# Sheet1.net
KiCad netlist of a schematic drawn in Altium Designer
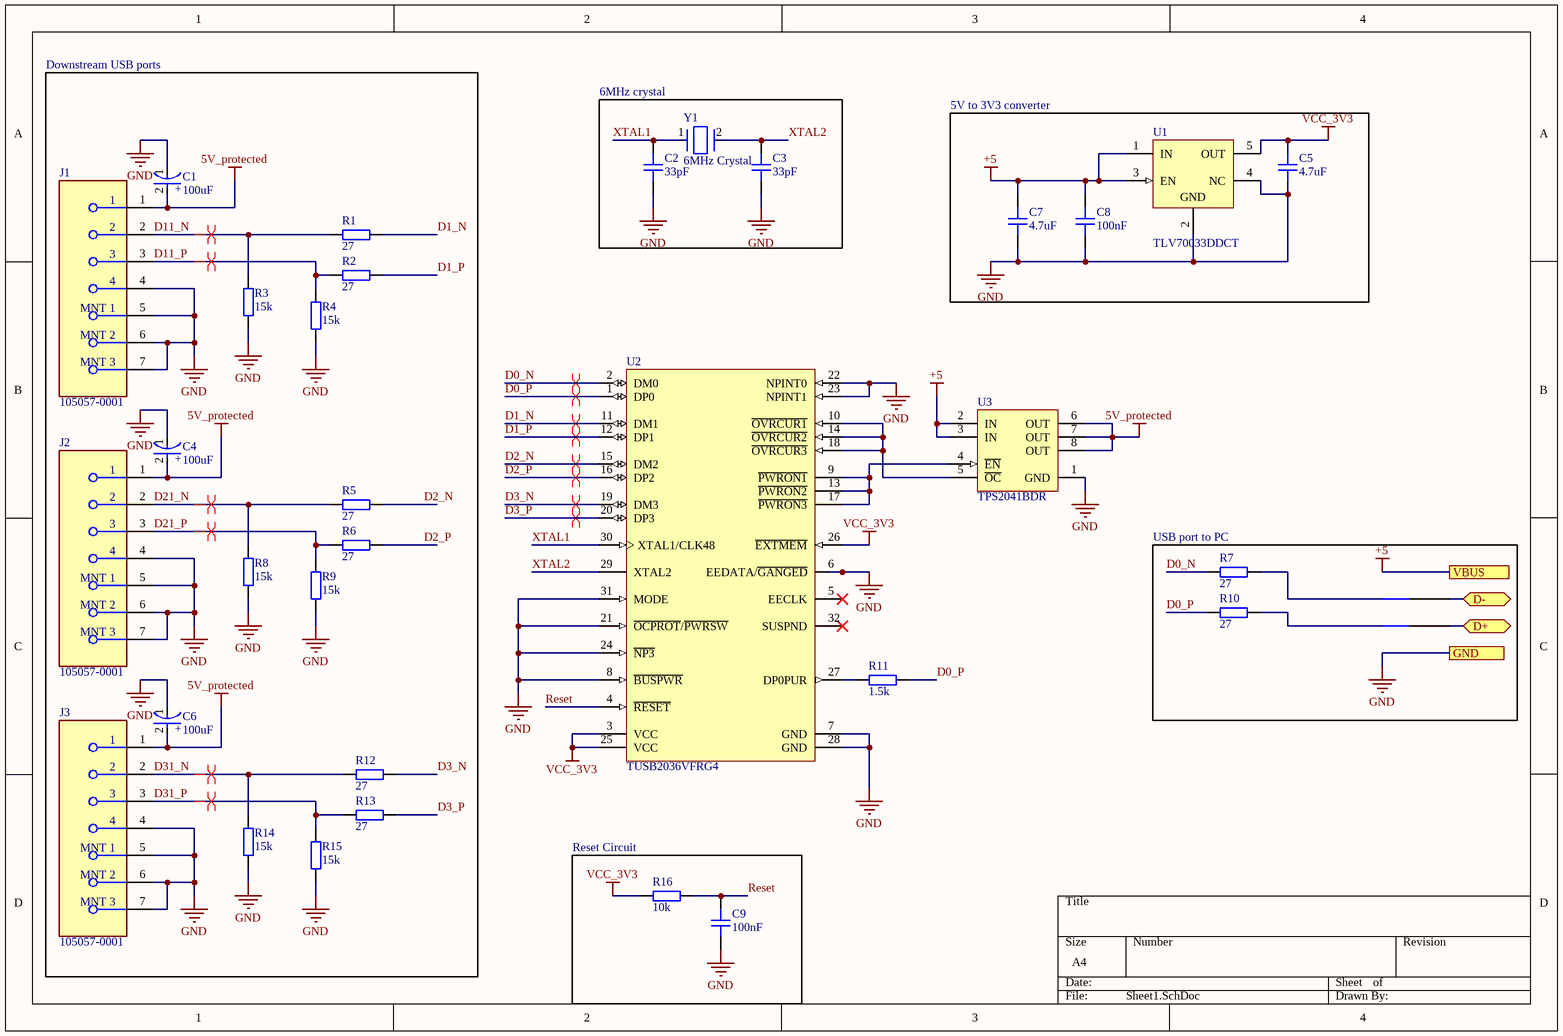
[diagram p0: Sheet1.SchDoc]

(export (version "E")
  (design (tool "Eeschema 10.0.6"))
  (components
    (comp (ref "C1")
      (value "100uF")
      (footprint "FP-TPSB-MFG")
      (description "CAP TANT 100UF 10% 6.3V 1411 TPSB107K006R0400")
      (fields (field (name "TOLERANCE") "10%") (field (name "VOLTAGE") "6.3V"))
      (libsource (lib "Altium Content Vault") (part "a00bbbee19879c290e62620ae7e47b1"))
    )
    (comp (ref "C2")
      (value "33pF")
      (footprint "CAP_0603")
      (description "Capacitor SMD 0603")
      (libsource (lib "Schematic-Lib-PhilsLab") (part "CAP_0603"))
    )
    (comp (ref "C3")
      (value "33pF")
      (footprint "CAP_0603")
      (description "Capacitor SMD 0603")
      (libsource (lib "Schematic-Lib-PhilsLab") (part "CAP_0603"))
    )
    (comp (ref "C4")
      (value "100uF")
      (footprint "FP-TPSB-MFG")
      (description "CAP TANT 100UF 10% 6.3V 1411 TPSB107K006R0400")
      (fields (field (name "TOLERANCE") "10%") (field (name "VOLTAGE") "6.3V"))
      (libsource (lib "Altium Content Vault") (part "a00bbbee19879c290e62620ae7e47b1"))
    )
    (comp (ref "C5")
      (value "4.7uF")
      (footprint "CAP_0603")
      (description "Capacitor SMD 0603")
      (libsource (lib "Schematic-Lib-PhilsLab") (part "CAP_0603"))
    )
    (comp (ref "C6")
      (value "100uF")
      (footprint "FP-TPSB-MFG")
      (description "CAP TANT 100UF 10% 6.3V 1411 TPSB107K006R0400")
      (fields (field (name "TOLERANCE") "10%") (field (name "VOLTAGE") "6.3V"))
      (libsource (lib "Altium Content Vault") (part "a00bbbee19879c290e62620ae7e47b1"))
    )
    (comp (ref "C7")
      (value "4.7uF")
      (footprint "CAP_0603")
      (description "Capacitor SMD 0603")
      (libsource (lib "Schematic-Lib-PhilsLab") (part "CAP_0603"))
    )
    (comp (ref "C8")
      (value "100nF")
      (footprint "CAP_0603")
      (description "Capacitor SMD 0603")
      (libsource (lib "Schematic-Lib-PhilsLab") (part "CAP_0603"))
    )
    (comp (ref "C9")
      (value "100nF")
      (footprint "CAP_0603")
      (description "Capacitor SMD 0603")
      (libsource (lib "Schematic-Lib-PhilsLab") (part "CAP_0603"))
    )
    (comp (ref "J1")
      (value "105057-0001")
      (footprint "FP-105057-0001-MFG")
      (description "USB - A USB 2.0 Receptacle Connector 4 Position Through Hole")
      (fields (field (name "MANUFACTURER") "Molex"))
      (libsource (lib "Altium Content Vault") (part "ae3a9d1ac18ec09d61ca50a90ac3895"))
    )
    (comp (ref "J2")
      (value "105057-0001")
      (footprint "FP-105057-0001-MFG")
      (description "USB - A USB 2.0 Receptacle Connector 4 Position Through Hole")
      (fields (field (name "MANUFACTURER") "Molex"))
      (libsource (lib "Altium Content Vault") (part "ae3a9d1ac18ec09d61ca50a90ac3895"))
    )
    (comp (ref "J3")
      (value "105057-0001")
      (footprint "FP-105057-0001-MFG")
      (description "USB - A USB 2.0 Receptacle Connector 4 Position Through Hole")
      (fields (field (name "MANUFACTURER") "Molex"))
      (libsource (lib "Altium Content Vault") (part "ae3a9d1ac18ec09d61ca50a90ac3895"))
    )
    (comp (ref "NT1")
      (value "NT")
      (footprint "NETTIE_SMD")
      (description "Net tie smd")
      (libsource (lib "Nick-Schematic-Lib") (part "NetTie_SMD"))
    )
    (comp (ref "NT2")
      (value "NT")
      (footprint "NETTIE_SMD")
      (description "Net tie smd")
      (libsource (lib "Nick-Schematic-Lib") (part "NetTie_SMD"))
    )
    (comp (ref "R1")
      (value "27")
      (footprint "RES_0603")
      (description "Resistor SMD 0603")
      (libsource (lib "Schematic-Lib-PhilsLab") (part "RES_0603"))
    )
    (comp (ref "R2")
      (value "27")
      (footprint "RES_0603")
      (description "Resistor SMD 0603")
      (libsource (lib "Schematic-Lib-PhilsLab") (part "RES_0603"))
    )
    (comp (ref "R3")
      (value "15k")
      (footprint "RES_0603")
      (description "Resistor SMD 0603")
      (libsource (lib "Schematic-Lib-PhilsLab") (part "RES_0603"))
    )
    (comp (ref "R4")
      (value "15k")
      (footprint "RES_0603")
      (description "Resistor SMD 0603")
      (libsource (lib "Schematic-Lib-PhilsLab") (part "RES_0603"))
    )
    (comp (ref "R5")
      (value "27")
      (footprint "RES_0603")
      (description "Resistor SMD 0603")
      (libsource (lib "Schematic-Lib-PhilsLab") (part "RES_0603"))
    )
    (comp (ref "R6")
      (value "27")
      (footprint "RES_0603")
      (description "Resistor SMD 0603")
      (libsource (lib "Schematic-Lib-PhilsLab") (part "RES_0603"))
    )
    (comp (ref "R7")
      (value "27")
      (footprint "RES_0603")
      (description "Resistor SMD 0603")
      (libsource (lib "Schematic-Lib-PhilsLab") (part "RES_0603"))
    )
    (comp (ref "R8")
      (value "15k")
      (footprint "RES_0603")
      (description "Resistor SMD 0603")
      (libsource (lib "Schematic-Lib-PhilsLab") (part "RES_0603"))
    )
    (comp (ref "R9")
      (value "15k")
      (footprint "RES_0603")
      (description "Resistor SMD 0603")
      (libsource (lib "Schematic-Lib-PhilsLab") (part "RES_0603"))
    )
    (comp (ref "R10")
      (value "27")
      (footprint "RES_0603")
      (description "Resistor SMD 0603")
      (libsource (lib "Schematic-Lib-PhilsLab") (part "RES_0603"))
    )
    (comp (ref "R11")
      (value "1.5k")
      (footprint "RES_0603")
      (description "Resistor SMD 0603")
      (libsource (lib "Schematic-Lib-PhilsLab") (part "RES_0603"))
    )
    (comp (ref "R12")
      (value "27")
      (footprint "RES_0603")
      (description "Resistor SMD 0603")
      (libsource (lib "Schematic-Lib-PhilsLab") (part "RES_0603"))
    )
    (comp (ref "R13")
      (value "27")
      (footprint "RES_0603")
      (description "Resistor SMD 0603")
      (libsource (lib "Schematic-Lib-PhilsLab") (part "RES_0603"))
    )
    (comp (ref "R14")
      (value "15k")
      (footprint "RES_0603")
      (description "Resistor SMD 0603")
      (libsource (lib "Schematic-Lib-PhilsLab") (part "RES_0603"))
    )
    (comp (ref "R15")
      (value "15k")
      (footprint "RES_0603")
      (description "Resistor SMD 0603")
      (libsource (lib "Schematic-Lib-PhilsLab") (part "RES_0603"))
    )
    (comp (ref "R16")
      (value "10k")
      (footprint "RES_0603")
      (description "Resistor SMD 0603")
      (libsource (lib "Schematic-Lib-PhilsLab") (part "RES_0603"))
    )
    (comp (ref "U1")
      (value "TLV70033DDCT")
      (footprint "DDC0005A_M")
      (fields (field (name "MANUFACTURER") "Texas Instruments"))
      (libsource (lib "Altium Content Vault") (part "TI-TXX7XXXX-5"))
    )
    (comp (ref "U2")
      (value "TUSB2036VFRG4")
      (footprint "VF32_N")
      (fields (field (name "MANUFACTURER") "Texas Instruments"))
      (libsource (lib "Altium Content Vault") (part "TI-TUSB2036-LQFP_VF-32"))
    )
    (comp (ref "U3")
      (value "TPS2041BDR")
      (footprint "D0008A_L")
      (fields (field (name "MANUFACTURER") "Texas Instruments"))
      (libsource (lib "Altium Content Vault") (part "TI-TPS2041BD8"))
    )
    (comp (ref "Y1")
      (value "6MHz Crystal")
      (footprint "FP-ABLS2-MFG")
      (description "CRYSTAL 6.0000MHZ 18PF SMD ABLS2-6.000MHZ-D4Y-T")
      (fields (field (name "TOLERANCE") "30ppm"))
      (libsource (lib "Altium Content Vault") (part "c23a69dc6c9e2f18f2079038eb95dd1"))
    )
  )
  (nets
    (net (code "1") (name "+5") (class "Default")
      (node (ref "C7") (pin "2") (pinfunction "2_2") (pintype "passive"))
      (node (ref "C8") (pin "2") (pinfunction "2_2") (pintype "passive"))
      (node (ref "U1") (pin "1") (pinfunction "IN_1") (pintype "power_in"))
      (node (ref "U1") (pin "3") (pinfunction "EN_3") (pintype "input"))
      (node (ref "U3") (pin "2") (pinfunction "IN_2") (pintype "power_in"))
      (node (ref "U3") (pin "3") (pinfunction "IN_3") (pintype "power_in"))
    )
    (net (code "4") (name "/D0_N") (class "Default")
      (node (ref "R7") (pin "1") (pinfunction "1_1") (pintype "passive"))
      (node (ref "U2") (pin "2") (pinfunction "DM0_2") (pintype "bidirectional"))
    )
    (net (code "5") (name "/D0_P") (class "Default")
      (node (ref "R10") (pin "1") (pinfunction "1_1") (pintype "passive"))
      (node (ref "R11") (pin "2") (pinfunction "2_2") (pintype "passive"))
      (node (ref "U2") (pin "1") (pinfunction "DP0_1") (pintype "bidirectional"))
    )
    (net (code "6") (name "/D1_N") (class "Default")
      (node (ref "R1") (pin "2") (pinfunction "2_2") (pintype "passive"))
      (node (ref "U2") (pin "11") (pinfunction "DM1_11") (pintype "bidirectional"))
    )
    (net (code "7") (name "/D1_P") (class "Default")
      (node (ref "R2") (pin "2") (pinfunction "2_2") (pintype "passive"))
      (node (ref "U2") (pin "12") (pinfunction "DP1_12") (pintype "bidirectional"))
    )
    (net (code "8") (name "/D2_N") (class "Default")
      (node (ref "R5") (pin "2") (pinfunction "2_2") (pintype "passive"))
      (node (ref "U2") (pin "15") (pinfunction "DM2_15") (pintype "bidirectional"))
    )
    (net (code "9") (name "/D2_P") (class "Default")
      (node (ref "R6") (pin "2") (pinfunction "2_2") (pintype "passive"))
      (node (ref "U2") (pin "16") (pinfunction "DP2_16") (pintype "bidirectional"))
    )
    (net (code "10") (name "/D3_N") (class "Default")
      (node (ref "R12") (pin "2") (pinfunction "2_2") (pintype "passive"))
      (node (ref "U2") (pin "19") (pinfunction "DM3_19") (pintype "bidirectional"))
    )
    (net (code "11") (name "/D3_P") (class "Default")
      (node (ref "R13") (pin "2") (pinfunction "2_2") (pintype "passive"))
      (node (ref "U2") (pin "20") (pinfunction "DP3_20") (pintype "bidirectional"))
    )
    (net (code "12") (name "/D11_N") (class "Default")
      (node (ref "J1") (pin "2") (pinfunction "2_2") (pintype "passive"))
      (node (ref "R1") (pin "1") (pinfunction "1_1") (pintype "passive"))
      (node (ref "R3") (pin "2") (pinfunction "2_2") (pintype "passive"))
    )
    (net (code "13") (name "/D11_P") (class "Default")
      (node (ref "J1") (pin "3") (pinfunction "3_3") (pintype "passive"))
      (node (ref "R2") (pin "1") (pinfunction "1_1") (pintype "passive"))
      (node (ref "R4") (pin "2") (pinfunction "2_2") (pintype "passive"))
    )
    (net (code "14") (name "/D21_N") (class "Default")
      (node (ref "J2") (pin "2") (pinfunction "2_2") (pintype "passive"))
      (node (ref "R5") (pin "1") (pinfunction "1_1") (pintype "passive"))
      (node (ref "R8") (pin "2") (pinfunction "2_2") (pintype "passive"))
    )
    (net (code "15") (name "/D21_P") (class "Default")
      (node (ref "J2") (pin "3") (pinfunction "3_3") (pintype "passive"))
      (node (ref "R6") (pin "1") (pinfunction "1_1") (pintype "passive"))
      (node (ref "R9") (pin "2") (pinfunction "2_2") (pintype "passive"))
    )
    (net (code "16") (name "/D31_N") (class "Default")
      (node (ref "J3") (pin "2") (pinfunction "2_2") (pintype "passive"))
      (node (ref "R12") (pin "1") (pinfunction "1_1") (pintype "passive"))
      (node (ref "R14") (pin "2") (pinfunction "2_2") (pintype "passive"))
    )
    (net (code "17") (name "/D31_P") (class "Default")
      (node (ref "J3") (pin "3") (pinfunction "3_3") (pintype "passive"))
      (node (ref "R13") (pin "1") (pinfunction "1_1") (pintype "passive"))
      (node (ref "R15") (pin "2") (pinfunction "2_2") (pintype "passive"))
    )
    (net (code "18") (name "/Reset") (class "Default")
      (node (ref "C9") (pin "2") (pinfunction "2_2") (pintype "passive"))
      (node (ref "R16") (pin "2") (pinfunction "2_2") (pintype "passive"))
      (node (ref "U2") (pin "4") (pinfunction "~{RESET}_4") (pintype "input"))
    )
    (net (code "19") (name "/XTAL1") (class "Default")
      (node (ref "C2") (pin "2") (pinfunction "2_2") (pintype "passive"))
      (node (ref "U2") (pin "30") (pinfunction "XTAL1/CLK48_30") (pintype "input"))
      (node (ref "Y1") (pin "1") (pinfunction "1_1") (pintype "passive"))
    )
    (net (code "20") (name "/XTAL2") (class "Default")
      (node (ref "C3") (pin "2") (pinfunction "2_2") (pintype "passive"))
      (node (ref "U2") (pin "29") (pinfunction "XTAL2_29") (pintype "passive"))
      (node (ref "Y1") (pin "2") (pinfunction "2_2") (pintype "passive"))
    )
    (net (code "21") (name "5V_protected") (class "Default")
      (node (ref "C1") (pin "2") (pinfunction "A_2") (pintype "passive"))
      (node (ref "C4") (pin "2") (pinfunction "A_2") (pintype "passive"))
      (node (ref "C6") (pin "2") (pinfunction "A_2") (pintype "passive"))
      (node (ref "J1") (pin "1") (pinfunction "1_1") (pintype "passive"))
      (node (ref "J2") (pin "1") (pinfunction "1_1") (pintype "passive"))
      (node (ref "J3") (pin "1") (pinfunction "1_1") (pintype "passive"))
      (node (ref "U3") (pin "6") (pinfunction "OUT_6") (pintype "power_in"))
      (node (ref "U3") (pin "7") (pinfunction "OUT_7") (pintype "power_in"))
      (node (ref "U3") (pin "8") (pinfunction "OUT_8") (pintype "power_in"))
    )
    (net (code "22") (name "GND") (class "Default")
      (node (ref "C1") (pin "1") (pinfunction "C_1") (pintype "passive"))
      (node (ref "C2") (pin "1") (pinfunction "1_1") (pintype "passive"))
      (node (ref "C3") (pin "1") (pinfunction "1_1") (pintype "passive"))
      (node (ref "C4") (pin "1") (pinfunction "C_1") (pintype "passive"))
      (node (ref "C5") (pin "1") (pinfunction "1_1") (pintype "passive"))
      (node (ref "C6") (pin "1") (pinfunction "C_1") (pintype "passive"))
      (node (ref "C7") (pin "1") (pinfunction "1_1") (pintype "passive"))
      (node (ref "C8") (pin "1") (pinfunction "1_1") (pintype "passive"))
      (node (ref "C9") (pin "1") (pinfunction "1_1") (pintype "passive"))
      (node (ref "J1") (pin "4") (pinfunction "4_4") (pintype "passive"))
      (node (ref "J1") (pin "5") (pinfunction "MNT_1_5") (pintype "passive"))
      (node (ref "J1") (pin "6") (pinfunction "MNT_2_6") (pintype "passive"))
      (node (ref "J1") (pin "7") (pinfunction "MNT_3_7") (pintype "passive"))
      (node (ref "J2") (pin "4") (pinfunction "4_4") (pintype "passive"))
      (node (ref "J2") (pin "5") (pinfunction "MNT_1_5") (pintype "passive"))
      (node (ref "J2") (pin "6") (pinfunction "MNT_2_6") (pintype "passive"))
      (node (ref "J2") (pin "7") (pinfunction "MNT_3_7") (pintype "passive"))
      (node (ref "J3") (pin "4") (pinfunction "4_4") (pintype "passive"))
      (node (ref "J3") (pin "5") (pinfunction "MNT_1_5") (pintype "passive"))
      (node (ref "J3") (pin "6") (pinfunction "MNT_2_6") (pintype "passive"))
      (node (ref "J3") (pin "7") (pinfunction "MNT_3_7") (pintype "passive"))
      (node (ref "R14") (pin "1") (pinfunction "1_1") (pintype "passive"))
      (node (ref "R15") (pin "1") (pinfunction "1_1") (pintype "passive"))
      (node (ref "R3") (pin "1") (pinfunction "1_1") (pintype "passive"))
      (node (ref "R4") (pin "1") (pinfunction "1_1") (pintype "passive"))
      (node (ref "R8") (pin "1") (pinfunction "1_1") (pintype "passive"))
      (node (ref "R9") (pin "1") (pinfunction "1_1") (pintype "passive"))
      (node (ref "U1") (pin "2") (pinfunction "GND_2") (pintype "passive"))
      (node (ref "U1") (pin "4") (pinfunction "NC_4") (pintype "passive"))
      (node (ref "U2") (pin "21") (pinfunction "~{OCPROT}/~{PWRSW}_21") (pintype "input"))
      (node (ref "U2") (pin "22") (pinfunction "NPINT0_22") (pintype "input"))
      (node (ref "U2") (pin "23") (pinfunction "NPINT1_23") (pintype "input"))
      (node (ref "U2") (pin "24") (pinfunction "~{NP3}_24") (pintype "input"))
      (node (ref "U2") (pin "28") (pinfunction "GND_28") (pintype "power_in"))
      (node (ref "U2") (pin "31") (pinfunction "MODE_31") (pintype "input"))
      (node (ref "U2") (pin "6") (pinfunction "EEDATA/~{GANGED}_6") (pintype "passive"))
      (node (ref "U2") (pin "7") (pinfunction "GND_7") (pintype "power_in"))
      (node (ref "U2") (pin "8") (pinfunction "~{BUSPWR}_8") (pintype "input"))
      (node (ref "U3") (pin "1") (pinfunction "GND_1") (pintype "power_in"))
    )
    (net (code "23") (name "Net-(NT1-Pad1)") (class "Default")
      (node (ref "NT1") (pin "1") (pinfunction "1_1") (pintype "passive"))
      (node (ref "R7") (pin "2") (pinfunction "2_2") (pintype "passive"))
    )
    (net (code "24") (name "Net-(NT2-Pad1)") (class "Default")
      (node (ref "NT2") (pin "1") (pinfunction "1_1") (pintype "passive"))
      (node (ref "R10") (pin "2") (pinfunction "2_2") (pintype "passive"))
    )
    (net (code "25") (name "Net-(U2-DP0PUR)") (class "Default")
      (node (ref "R11") (pin "1") (pinfunction "1_1") (pintype "passive"))
      (node (ref "U2") (pin "27") (pinfunction "DP0PUR_27") (pintype "output"))
    )
    (net (code "26") (name "Net-(U2-~{OVRCUR1})") (class "Default")
      (node (ref "U2") (pin "10") (pinfunction "~{OVRCUR1}_10") (pintype "input"))
      (node (ref "U2") (pin "14") (pinfunction "~{OVRCUR2}_14") (pintype "input"))
      (node (ref "U2") (pin "18") (pinfunction "~{OVRCUR3}_18") (pintype "input"))
      (node (ref "U3") (pin "5") (pinfunction "~{OC}_5") (pintype "open_collector"))
    )
    (net (code "27") (name "Net-(U2-~{PWRON1})") (class "Default")
      (node (ref "U2") (pin "13") (pinfunction "~{PWRON2}_13") (pintype "open_collector"))
      (node (ref "U2") (pin "17") (pinfunction "~{PWRON3}_17") (pintype "open_collector"))
      (node (ref "U2") (pin "9") (pinfunction "~{PWRON1}_9") (pintype "open_collector"))
      (node (ref "U3") (pin "4") (pinfunction "~{EN}_4") (pintype "input"))
    )
    (net (code "28") (name "VCC_3V3") (class "Default")
      (node (ref "C5") (pin "2") (pinfunction "2_2") (pintype "passive"))
      (node (ref "R16") (pin "1") (pinfunction "1_1") (pintype "passive"))
      (node (ref "U1") (pin "5") (pinfunction "OUT_5") (pintype "power_in"))
      (node (ref "U2") (pin "25") (pinfunction "VCC_25") (pintype "power_in"))
      (node (ref "U2") (pin "26") (pinfunction "~{EXTMEM}_26") (pintype "input"))
      (node (ref "U2") (pin "3") (pinfunction "VCC_3") (pintype "power_in"))
    )
    (net (code "29") (name "unconnected-(NT1-Pad2)") (class "Default")
      (node (ref "NT1") (pin "2") (pinfunction "2_2") (pintype "passive"))
    )
    (net (code "30") (name "unconnected-(NT2-Pad2)") (class "Default")
      (node (ref "NT2") (pin "2") (pinfunction "2_2") (pintype "passive"))
    )
    (net (code "31") (name "unconnected-(U2-EECLK-Pad5)") (class "Default")
      (node (ref "U2") (pin "5") (pinfunction "EECLK_5") (pintype "tri_state+no_connect"))
    )
    (net (code "32") (name "unconnected-(U2-SUSPND-Pad32)") (class "Default")
      (node (ref "U2") (pin "32") (pinfunction "SUSPND_32") (pintype "passive+no_connect"))
    )
  )
)
